# Sch_L298n.net
KiCad netlist of a schematic drawn in Altium Designer
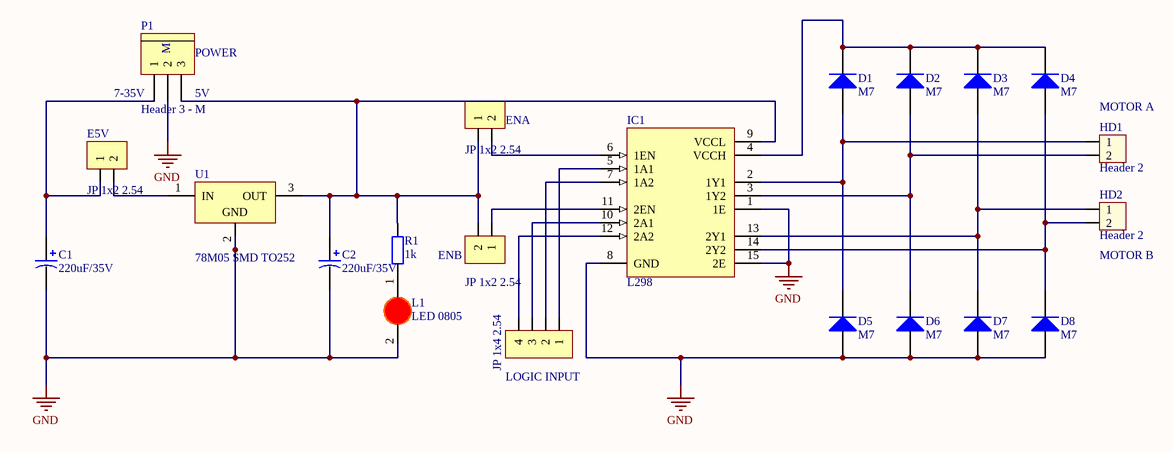
[diagram p0: Sch_L298n.SchDoc]

(export (version "E")
  (design (tool "Eeschema 10.0.6"))
  (components
    (comp (ref "C1")
      (value "220uF/35V")
      (footprint "CAP_ALUM_SMD_80102_TYPE_F")
      (description "CAP ALUM 220uF 20% 35V SMD")
      (fields (field (name "MPN") "EEE-FK1V221P") (field (name "MFR") "Panasonic"))
      (libsource (lib "BYTECH_HW_LIB_2019 (1)") (part "EEE-FK1V221P"))
    )
    (comp (ref "C2")
      (value "220uF/35V")
      (footprint "CAP_ALUM_SMD_80102_TYPE_F")
      (description "CAP ALUM 220uF 20% 35V SMD")
      (fields (field (name "MPN") "EEE-FK1V221P") (field (name "MFR") "Panasonic"))
      (libsource (lib "BYTECH_HW_LIB_2019 (1)") (part "EEE-FK1V221P"))
    )
    (comp (ref "D1")
      (value "M7")
      (footprint "DIODE SMA")
      (description "Dán")
      (libsource (lib "Diode") (part "Diode M7 ( 4007 )"))
    )
    (comp (ref "D2")
      (value "M7")
      (footprint "DIODE SMA")
      (description "Dán")
      (libsource (lib "Diode") (part "Diode M7 ( 4007 )"))
    )
    (comp (ref "D3")
      (value "M7")
      (footprint "DIODE SMA")
      (description "Dán")
      (libsource (lib "Diode") (part "Diode M7 ( 4007 )"))
    )
    (comp (ref "D4")
      (value "M7")
      (footprint "DIODE SMA")
      (description "Dán")
      (libsource (lib "Diode") (part "Diode M7 ( 4007 )"))
    )
    (comp (ref "D5")
      (value "M7")
      (footprint "DIODE SMA")
      (description "Dán")
      (libsource (lib "Diode") (part "Diode M7 ( 4007 )"))
    )
    (comp (ref "D6")
      (value "M7")
      (footprint "DIODE SMA")
      (description "Dán")
      (libsource (lib "Diode") (part "Diode M7 ( 4007 )"))
    )
    (comp (ref "D7")
      (value "M7")
      (footprint "DIODE SMA")
      (description "Dán")
      (libsource (lib "Diode") (part "Diode M7 ( 4007 )"))
    )
    (comp (ref "D8")
      (value "M7")
      (footprint "DIODE SMA")
      (description "Dán")
      (libsource (lib "Diode") (part "Diode M7 ( 4007 )"))
    )
    (comp (ref "HD1")
      (value "Header 2")
      (footprint "HED2")
      (description "Header 2 (Green)")
      (libsource (lib "syhaunguyen") (part "Hed2"))
    )
    (comp (ref "HD2")
      (value "Header 2")
      (footprint "HED2")
      (description "Header 2 (Green)")
      (libsource (lib "syhaunguyen") (part "Hed2"))
    )
    (comp (ref "IC1")
      (value "L298")
      (footprint "DIP15SL2")
      (description "Dual Full-H Driver")
      (fields (field (name "PUBLISHER") "Altium Limited"))
      (libsource (lib "syhaunguyen") (part "L298"))
    )
    (comp (ref "JP1")
      (value "JP 1x2 2.54")
      (footprint "JP 1x2 CT")
      (description "Cắm")
      (libsource (lib "") (part "JP 1x2 2.54 Cai Thang_1"))
    )
    (comp (ref "JP2")
      (value "JP 1x2 2.54")
      (footprint "JP 1x2 CT")
      (description "Cắm")
      (libsource (lib "") (part "JP 1x2 2.54 Cai Thang_1"))
    )
    (comp (ref "JP3")
      (value "JP 1x2 2.54")
      (footprint "JP 1x2 CT")
      (description "Cắm")
      (libsource (lib "Jump") (part "JP 1x2 2.54 Cai Thang"))
    )
    (comp (ref "JP4")
      (value "JP 1x4 2.54")
      (footprint "JP 1x4 DT")
      (description "Cắm")
      (libsource (lib "Jump") (part "JP 1x4 2.54 Duc Thang"))
    )
    (comp (ref "L1")
      (value "LED 0805")
      (footprint "LED-0805-Red")
      (description "Dán")
      (libsource (lib "Led") (part "LED 0805 Do"))
    )
    (comp (ref "P1")
      (value "Header 3 - M")
      (footprint "Medium - Header 3")
      (description "Header, 3-Pin, Medium")
      (fields (field (name "PUBLISHER") "Altium Limited"))
      (libsource (lib "BYTECH_HW_LIB_2019 (1)") (part "Header 3 - M"))
    )
    (comp (ref "R1")
      (value "1k")
      (footprint "tro smd 0603")
      (description "Dán")
      (libsource (lib "Dien Tro") (part "Tro 0603 5% 1k"))
    )
    (comp (ref "U1")
      (value "78M05 SMD TO252")
      (footprint "TO252")
      (description "Dán")
      (libsource (lib "IC") (part "78M05 SMD TO252"))
    )
  )
  (nets
    (net (code "1") (name "GND") (class "Default")
      (node (ref "C1") (pin "2") (pinfunction "2_2") (pintype "passive"))
      (node (ref "C2") (pin "2") (pinfunction "2_2") (pintype "passive"))
      (node (ref "D5") (pin "1") (pinfunction "A_1") (pintype "passive"))
      (node (ref "D6") (pin "1") (pinfunction "A_1") (pintype "passive"))
      (node (ref "D7") (pin "1") (pinfunction "A_1") (pintype "passive"))
      (node (ref "D8") (pin "1") (pinfunction "A_1") (pintype "passive"))
      (node (ref "IC1") (pin "1") (pinfunction "1E_1") (pintype "passive"))
      (node (ref "IC1") (pin "15") (pinfunction "2E_15") (pintype "passive"))
      (node (ref "IC1") (pin "8") (pinfunction "GND_8") (pintype "power_in"))
      (node (ref "L1") (pin "2") (pinfunction "K_2") (pintype "passive"))
      (node (ref "P1") (pin "2") (pinfunction "2_2") (pintype "passive"))
      (node (ref "U1") (pin "2") (pinfunction "GND_2") (pintype "power_in"))
    )
    (net (code "2") (name "Net-(C1-Pad1)") (class "Default")
      (node (ref "C1") (pin "1") (pinfunction "1_1") (pintype "passive"))
      (node (ref "JP2") (pin "1") (pinfunction "1_1") (pintype "passive"))
      (node (ref "P1") (pin "1") (pinfunction "1_1") (pintype "passive"))
    )
    (net (code "3") (name "Net-(D1-A)") (class "Default")
      (node (ref "D1") (pin "1") (pinfunction "A_1") (pintype "passive"))
      (node (ref "D5") (pin "2") (pinfunction "K_2") (pintype "passive"))
      (node (ref "HD1") (pin "1") (pinfunction "1_1") (pintype "passive"))
      (node (ref "IC1") (pin "2") (pinfunction "1Y1_2") (pintype "tri_state"))
    )
    (net (code "4") (name "Net-(D1-K)") (class "Default")
      (node (ref "D1") (pin "2") (pinfunction "K_2") (pintype "passive"))
      (node (ref "D2") (pin "2") (pinfunction "K_2") (pintype "passive"))
      (node (ref "D3") (pin "2") (pinfunction "K_2") (pintype "passive"))
      (node (ref "D4") (pin "2") (pinfunction "K_2") (pintype "passive"))
      (node (ref "IC1") (pin "4") (pinfunction "VCCH_4") (pintype "power_in"))
    )
    (net (code "5") (name "Net-(D2-A)") (class "Default")
      (node (ref "D2") (pin "1") (pinfunction "A_1") (pintype "passive"))
      (node (ref "D6") (pin "2") (pinfunction "K_2") (pintype "passive"))
      (node (ref "HD1") (pin "2") (pinfunction "2_2") (pintype "passive"))
      (node (ref "IC1") (pin "3") (pinfunction "1Y2_3") (pintype "tri_state"))
    )
    (net (code "6") (name "Net-(D3-A)") (class "Default")
      (node (ref "D3") (pin "1") (pinfunction "A_1") (pintype "passive"))
      (node (ref "D7") (pin "2") (pinfunction "K_2") (pintype "passive"))
      (node (ref "HD2") (pin "1") (pinfunction "1_1") (pintype "passive"))
      (node (ref "IC1") (pin "13") (pinfunction "2Y1_13") (pintype "tri_state"))
    )
    (net (code "7") (name "Net-(D4-A)") (class "Default")
      (node (ref "D4") (pin "1") (pinfunction "A_1") (pintype "passive"))
      (node (ref "D8") (pin "2") (pinfunction "K_2") (pintype "passive"))
      (node (ref "HD2") (pin "2") (pinfunction "2_2") (pintype "passive"))
      (node (ref "IC1") (pin "14") (pinfunction "2Y2_14") (pintype "tri_state"))
    )
    (net (code "8") (name "Net-(IC1-1A1)") (class "Default")
      (node (ref "IC1") (pin "5") (pinfunction "1A1_5") (pintype "input"))
      (node (ref "JP4") (pin "1") (pinfunction "1_1") (pintype "passive"))
    )
    (net (code "9") (name "Net-(IC1-1A2)") (class "Default")
      (node (ref "IC1") (pin "7") (pinfunction "1A2_7") (pintype "input"))
      (node (ref "JP4") (pin "2") (pinfunction "2_2") (pintype "passive"))
    )
    (net (code "10") (name "Net-(IC1-1EN)") (class "Default")
      (node (ref "IC1") (pin "6") (pinfunction "1EN_6") (pintype "input"))
      (node (ref "JP1") (pin "2") (pinfunction "2_2") (pintype "passive"))
    )
    (net (code "11") (name "Net-(IC1-2A1)") (class "Default")
      (node (ref "IC1") (pin "10") (pinfunction "2A1_10") (pintype "input"))
      (node (ref "JP4") (pin "3") (pinfunction "3_3") (pintype "passive"))
    )
    (net (code "12") (name "Net-(IC1-2A2)") (class "Default")
      (node (ref "IC1") (pin "12") (pinfunction "2A2_12") (pintype "input"))
      (node (ref "JP4") (pin "4") (pinfunction "4_4") (pintype "passive"))
    )
    (net (code "13") (name "Net-(IC1-2EN)") (class "Default")
      (node (ref "IC1") (pin "11") (pinfunction "2EN_11") (pintype "input"))
      (node (ref "JP3") (pin "1") (pinfunction "1_1") (pintype "passive"))
    )
    (net (code "14") (name "Net-(IC1-VCCL)") (class "Default")
      (node (ref "C2") (pin "1") (pinfunction "1_1") (pintype "passive"))
      (node (ref "IC1") (pin "9") (pinfunction "VCCL_9") (pintype "power_in"))
      (node (ref "JP1") (pin "1") (pinfunction "1_1") (pintype "passive"))
      (node (ref "JP3") (pin "2") (pinfunction "2_2") (pintype "passive"))
      (node (ref "P1") (pin "3") (pinfunction "3_3") (pintype "passive"))
      (node (ref "R1") (pin "2") (pinfunction "2_2") (pintype "passive"))
      (node (ref "U1") (pin "3") (pinfunction "OUT_3") (pintype "power_in"))
    )
    (net (code "15") (name "Net-(L1-A)") (class "Default")
      (node (ref "L1") (pin "1") (pinfunction "A_1") (pintype "passive"))
      (node (ref "R1") (pin "1") (pinfunction "1_1") (pintype "passive"))
    )
    (net (code "16") (name "Net-(U1-IN)") (class "Default")
      (node (ref "JP2") (pin "2") (pinfunction "2_2") (pintype "passive"))
      (node (ref "U1") (pin "1") (pinfunction "IN_1") (pintype "power_in"))
    )
  )
)
